# 05_FEEDBACK_OUTPUTS.net
KiCad netlist of a schematic drawn in Altium Designer
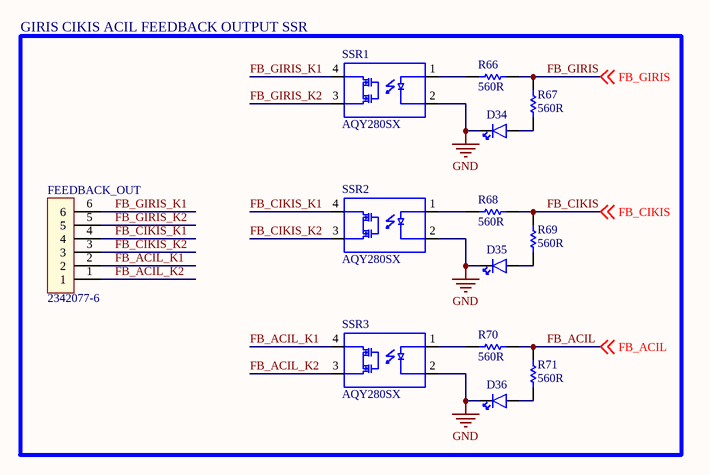
[diagram p0: 05_FEEDBACK_OUTPUTS.SchDoc]

(export (version "E")
  (design (tool "Eeschema 10.0.6"))
  (components
    (comp (ref "D34")
      (value "led_green")
      (footprint "805LED")
      (description "LED 2X1.2MM 570NM GN WTR CLR SMD")
      (fields (field (name "DIGI-KEY PART NUMBER") "754-1127-1-ND"))
      (libsource (lib "FKDZ_Altium_Lib") (part "LED_GREEN_0805"))
    )
    (comp (ref "D35")
      (value "led_green")
      (footprint "805LED")
      (description "LED 2X1.2MM 570NM GN WTR CLR SMD")
      (fields (field (name "DIGI-KEY PART NUMBER") "754-1127-1-ND"))
      (libsource (lib "FKDZ_Altium_Lib") (part "LED_GREEN_0805"))
    )
    (comp (ref "D36")
      (value "led_green")
      (footprint "805LED")
      (description "LED 2X1.2MM 570NM GN WTR CLR SMD")
      (fields (field (name "DIGI-KEY PART NUMBER") "754-1127-1-ND"))
      (libsource (lib "FKDZ_Altium_Lib") (part "LED_GREEN_0805"))
    )
    (comp (ref "FEEDBACK_OUT")
      (value "2342077-6")
      (footprint "TERM BLOCK HDR 6POS 90DEG PITCH 3.81MM")
      (fields
        (field (name "DIGI-KEY PART NUMBER") "A145325-ND")
        (field (name "MANUFACTURER") "TE Connectivity AMP Connectors")
      )
      (libsource (lib "FKDZ_Altium_Lib") (part "TERM BLOCK HDR 6POS 90DEG 3.81MM"))
    )
    (comp (ref "R66")
      (value "560R")
      (footprint "603R")
      (description "560 Ohms ±5% 0.1W, 1/10W Chip Resistor 0603 (1608 Metric) Moisture Resistant Thick Film")
      (fields (field (name "DIGI-KEY PART NUMBER") "311-560GRCT-ND") (field (name "MANUFACTURER") "Yageo"))
      (libsource (lib "FKDZ_Altium_Lib") (part "RES_560_OHM_%5_0.1W_0603"))
    )
    (comp (ref "R67")
      (value "560R")
      (footprint "603R")
      (description "560 Ohms ±5% 0.1W, 1/10W Chip Resistor 0603 (1608 Metric) Moisture Resistant Thick Film")
      (fields (field (name "DIGI-KEY PART NUMBER") "311-560GRCT-ND") (field (name "MANUFACTURER") "Yageo"))
      (libsource (lib "FKDZ_Altium_Lib") (part "RES_560_OHM_%5_0.1W_0603"))
    )
    (comp (ref "R68")
      (value "560R")
      (footprint "603R")
      (description "560 Ohms ±5% 0.1W, 1/10W Chip Resistor 0603 (1608 Metric) Moisture Resistant Thick Film")
      (fields (field (name "DIGI-KEY PART NUMBER") "311-560GRCT-ND") (field (name "MANUFACTURER") "Yageo"))
      (libsource (lib "FKDZ_Altium_Lib") (part "RES_560_OHM_%5_0.1W_0603"))
    )
    (comp (ref "R69")
      (value "560R")
      (footprint "603R")
      (description "560 Ohms ±5% 0.1W, 1/10W Chip Resistor 0603 (1608 Metric) Moisture Resistant Thick Film")
      (fields (field (name "DIGI-KEY PART NUMBER") "311-560GRCT-ND") (field (name "MANUFACTURER") "Yageo"))
      (libsource (lib "FKDZ_Altium_Lib") (part "RES_560_OHM_%5_0.1W_0603"))
    )
    (comp (ref "R70")
      (value "560R")
      (footprint "603R")
      (description "560 Ohms ±5% 0.1W, 1/10W Chip Resistor 0603 (1608 Metric) Moisture Resistant Thick Film")
      (fields (field (name "DIGI-KEY PART NUMBER") "311-560GRCT-ND") (field (name "MANUFACTURER") "Yageo"))
      (libsource (lib "FKDZ_Altium_Lib") (part "RES_560_OHM_%5_0.1W_0603"))
    )
    (comp (ref "R71")
      (value "560R")
      (footprint "603R")
      (description "560 Ohms ±5% 0.1W, 1/10W Chip Resistor 0603 (1608 Metric) Moisture Resistant Thick Film")
      (fields (field (name "DIGI-KEY PART NUMBER") "311-560GRCT-ND") (field (name "MANUFACTURER") "Yageo"))
      (libsource (lib "FKDZ_Altium_Lib") (part "RES_560_OHM_%5_0.1W_0603"))
    )
    (comp (ref "SSR1")
      (value "AQY280SX")
      (footprint "SOP254P680X220-4N")
      (description "Solid State SPST-NO (1 Form A) AC/DC 0-350V 150mA 4-SOP (0.173\", 4.40mm)")
      (fields
        (field (name "DIGI-KEY PART NUMBER") "255-3913-1-ND")
        (field (name "MANUFACTURER") "Panasonic Electric Works")
      )
      (libsource (lib "FKDZ_Altium_Lib") (part "SSR RELAY SPST-NO 120MA 0-350V AQY280SX"))
    )
    (comp (ref "SSR2")
      (value "AQY280SX")
      (footprint "SOP254P680X220-4N")
      (description "Solid State SPST-NO (1 Form A) AC/DC 0-350V 150mA 4-SOP (0.173\", 4.40mm)")
      (fields
        (field (name "DIGI-KEY PART NUMBER") "255-3913-1-ND")
        (field (name "MANUFACTURER") "Panasonic Electric Works")
      )
      (libsource (lib "FKDZ_Altium_Lib") (part "SSR RELAY SPST-NO 120MA 0-350V AQY280SX"))
    )
    (comp (ref "SSR3")
      (value "AQY280SX")
      (footprint "SOP254P680X220-4N")
      (description "Solid State SPST-NO (1 Form A) AC/DC 0-350V 150mA 4-SOP (0.173\", 4.40mm)")
      (fields
        (field (name "DIGI-KEY PART NUMBER") "255-3913-1-ND")
        (field (name "MANUFACTURER") "Panasonic Electric Works")
      )
      (libsource (lib "FKDZ_Altium_Lib") (part "SSR RELAY SPST-NO 120MA 0-350V AQY280SX"))
    )
  )
  (nets
    (net (code "1") (name "/FB_ACIL_K1") (class "Default")
      (node (ref "FEEDBACK_OUT") (pin "2") (pinfunction "2_2") (pintype "passive"))
      (node (ref "SSR3") (pin "4") (pinfunction "4_4") (pintype "passive"))
    )
    (net (code "2") (name "/FB_ACIL_K2") (class "Default")
      (node (ref "FEEDBACK_OUT") (pin "1") (pinfunction "1_1") (pintype "passive"))
      (node (ref "SSR3") (pin "3") (pinfunction "3_3") (pintype "passive"))
    )
    (net (code "3") (name "/FB_CIKIS_K1") (class "Default")
      (node (ref "FEEDBACK_OUT") (pin "4") (pinfunction "4_4") (pintype "passive"))
      (node (ref "SSR2") (pin "4") (pinfunction "4_4") (pintype "passive"))
    )
    (net (code "4") (name "/FB_CIKIS_K2") (class "Default")
      (node (ref "FEEDBACK_OUT") (pin "3") (pinfunction "3_3") (pintype "passive"))
      (node (ref "SSR2") (pin "3") (pinfunction "3_3") (pintype "passive"))
    )
    (net (code "5") (name "/FB_GIRIS_K1") (class "Default")
      (node (ref "FEEDBACK_OUT") (pin "6") (pinfunction "6_6") (pintype "passive"))
      (node (ref "SSR1") (pin "4") (pinfunction "4_4") (pintype "passive"))
    )
    (net (code "6") (name "/FB_GIRIS_K2") (class "Default")
      (node (ref "FEEDBACK_OUT") (pin "5") (pinfunction "5_5") (pintype "passive"))
      (node (ref "SSR1") (pin "3") (pinfunction "3_3") (pintype "passive"))
    )
    (net (code "7") (name "FB_ACIL") (class "Default")
      (node (ref "R70") (pin "1") (pinfunction "1_1") (pintype "passive"))
      (node (ref "R71") (pin "2") (pinfunction "2_2") (pintype "passive"))
    )
    (net (code "8") (name "FB_CIKIS") (class "Default")
      (node (ref "R68") (pin "1") (pinfunction "1_1") (pintype "passive"))
      (node (ref "R69") (pin "2") (pinfunction "2_2") (pintype "passive"))
    )
    (net (code "9") (name "FB_GIRIS") (class "Default")
      (node (ref "R66") (pin "1") (pinfunction "1_1") (pintype "passive"))
      (node (ref "R67") (pin "2") (pinfunction "2_2") (pintype "passive"))
    )
    (net (code "10") (name "GND") (class "Default")
      (node (ref "D34") (pin "2") (pinfunction "K_2") (pintype "passive"))
      (node (ref "D35") (pin "2") (pinfunction "K_2") (pintype "passive"))
      (node (ref "D36") (pin "2") (pinfunction "K_2") (pintype "passive"))
      (node (ref "SSR1") (pin "2") (pinfunction "2_2") (pintype "passive"))
      (node (ref "SSR2") (pin "2") (pinfunction "2_2") (pintype "passive"))
      (node (ref "SSR3") (pin "2") (pinfunction "2_2") (pintype "passive"))
    )
    (net (code "11") (name "Net-(D34-A)") (class "Default")
      (node (ref "D34") (pin "1") (pinfunction "A_1") (pintype "passive"))
      (node (ref "R67") (pin "1") (pinfunction "1_1") (pintype "passive"))
    )
    (net (code "12") (name "Net-(D35-A)") (class "Default")
      (node (ref "D35") (pin "1") (pinfunction "A_1") (pintype "passive"))
      (node (ref "R69") (pin "1") (pinfunction "1_1") (pintype "passive"))
    )
    (net (code "13") (name "Net-(D36-A)") (class "Default")
      (node (ref "D36") (pin "1") (pinfunction "A_1") (pintype "passive"))
      (node (ref "R71") (pin "1") (pinfunction "1_1") (pintype "passive"))
    )
    (net (code "14") (name "Net-(R66-Pad2)") (class "Default")
      (node (ref "R66") (pin "2") (pinfunction "2_2") (pintype "passive"))
      (node (ref "SSR1") (pin "1") (pinfunction "1_1") (pintype "passive"))
    )
    (net (code "15") (name "Net-(R68-Pad2)") (class "Default")
      (node (ref "R68") (pin "2") (pinfunction "2_2") (pintype "passive"))
      (node (ref "SSR2") (pin "1") (pinfunction "1_1") (pintype "passive"))
    )
    (net (code "16") (name "Net-(R70-Pad2)") (class "Default")
      (node (ref "R70") (pin "2") (pinfunction "2_2") (pintype "passive"))
      (node (ref "SSR3") (pin "1") (pinfunction "1_1") (pintype "passive"))
    )
  )
)
